# led-relay.net
KiCad netlist of a schematic drawn in Altium Designer
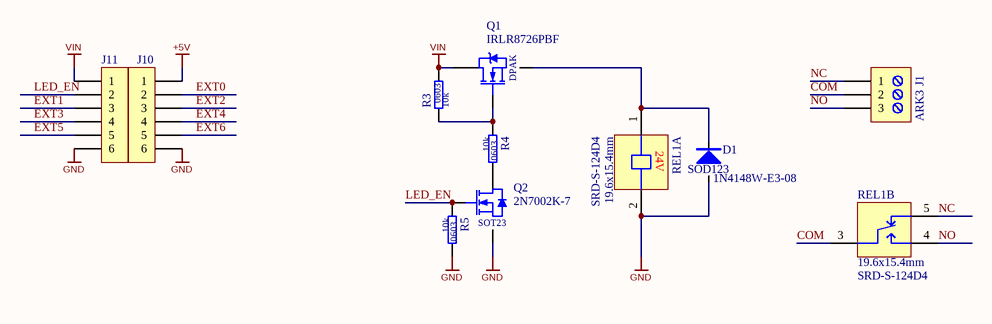
[diagram p0: led-relay.SchDoc]

(export (version "E")
  (design (tool "Eeschema 10.0.6"))
  (components
    (comp (ref "D1")
      (value "1N4148W-E3-08")
      (footprint "SOD123")
      (fields
        (field (name "SCH_FOOTPRINT") "SOD123")
        (field (name "PART NUMBER") "D_1N4148W_0A15_75V_SOD123")
        (field (name "VOLTAGE") "75")
        (field (name "MANUFACTURER") "Vishay")
      )
      (libsource (lib "Library") (part "D"))
    )
    (comp (ref "J1")
      (value "ARK3")
      (footprint "J_ARK3")
      (description "ARK Screw terminal, 3-Pin")
      (fields
        (field (name "SCH_FOOTPRINT") "ARK3")
        (field (name "PART NUMBER") "J_TB-5.0-P-3P")
        (field (name "MANUFACTURER") "DEGSON ELECTRONICS")
      )
      (libsource (lib "Library") (part "J_ARK3"))
    )
    (comp (ref "J10")
      (value "Goldpin")
      (footprint "P_HEADER_1x6_2.54")
      (description "Pin Header")
      (fields (field (name "PART NUMBER") "P_HEADER_1x6_2.54") (field (name "MANUFACTURER") "Connfly"))
      (libsource (lib "Library") (part "P_HEADER_1x6"))
    )
    (comp (ref "J11")
      (value "Goldpin")
      (footprint "P_HEADER_1x6_2.54")
      (description "Pin Header")
      (fields (field (name "PART NUMBER") "P_HEADER_1x6_2.54") (field (name "MANUFACTURER") "Connfly"))
      (libsource (lib "") (part "P_HEADER_1x6_1"))
    )
    (comp (ref "Q1")
      (value "IRLR8726PBF")
      (footprint "DPAK_TO252-3_SC63_M")
      (fields
        (field (name "SCH_FOOTPRINT") "DPAK")
        (field (name "PART NUMBER") "QNS_IRLR8726PBF")
        (field (name "VOLTAGE") "30V")
        (field (name "MANUFACTURER") "Infineon")
      )
      (libsource (lib "Library") (part "QNS_GDS"))
    )
    (comp (ref "Q2")
      (value "2N7002K-7")
      (footprint "SOT23_TO236_SC59")
      (fields
        (field (name "SCH_FOOTPRINT") "SOT23")
        (field (name "PART NUMBER") "QN_2N7002K-7")
        (field (name "VOLTAGE") "60V")
        (field (name "MANUFACTURER") "Diodes Inc")
      )
      (libsource (lib "Library") (part "QN_GSD"))
    )
    (comp (ref "R3")
      (value "10k")
      (footprint "R_0603_1608")
      (fields
        (field (name "SCH_FOOTPRINT") "0603")
        (field (name "PART NUMBER") "R_10k_0603_1")
        (field (name "VOLTAGE") "75V")
        (field (name "POWER") "100mW")
      )
      (libsource (lib "Library") (part "R"))
    )
    (comp (ref "R4")
      (value "10k")
      (footprint "R_0603_1608")
      (fields
        (field (name "SCH_FOOTPRINT") "0603")
        (field (name "PART NUMBER") "R_10k_0603_1")
        (field (name "VOLTAGE") "75V")
        (field (name "POWER") "100mW")
      )
      (libsource (lib "Library") (part "R"))
    )
    (comp (ref "R5")
      (value "10k")
      (footprint "R_0603_1608")
      (fields
        (field (name "SCH_FOOTPRINT") "0603")
        (field (name "PART NUMBER") "R_10k_0603_1")
        (field (name "VOLTAGE") "75V")
        (field (name "POWER") "100mW")
      )
      (libsource (lib "Library") (part "R"))
    )
    (comp (ref "REL1")
      (value "SRD-S-124D4")
      (footprint "SRD-S-124D4")
      (fields
        (field (name "SCH_FOOTPRINT") "19.6x15.4mm")
        (field (name "PART NUMBER") "REL_SRD-S-124D4")
        (field (name "VOLTAGE") "24V")
        (field (name "MANUFACTURER") "Sanyou")
      )
      (libsource (lib "Library") (part "REL_SRD-S-124D4"))
    )
  )
  (nets
    (net (code "1") (name "+5V") (class "Default")
      (node (ref "J10") (pin "1") (pinfunction "1_1") (pintype "passive"))
    )
    (net (code "2") (name "/COM") (class "Default")
      (node (ref "J1") (pin "2") (pinfunction "2_2") (pintype "passive"))
      (node (ref "REL1") (pin "3") (pinfunction "3_3") (pintype "passive"))
    )
    (net (code "3") (name "/EXT0") (class "Default")
      (node (ref "J10") (pin "2") (pinfunction "2_2") (pintype "passive"))
    )
    (net (code "4") (name "/EXT1") (class "Default")
      (node (ref "J11") (pin "3") (pinfunction "3_3") (pintype "passive"))
    )
    (net (code "5") (name "/EXT2") (class "Default")
      (node (ref "J10") (pin "3") (pinfunction "3_3") (pintype "passive"))
    )
    (net (code "6") (name "/EXT3") (class "Default")
      (node (ref "J11") (pin "4") (pinfunction "4_4") (pintype "passive"))
    )
    (net (code "7") (name "/EXT4") (class "Default")
      (node (ref "J10") (pin "4") (pinfunction "4_4") (pintype "passive"))
    )
    (net (code "8") (name "/EXT5") (class "Default")
      (node (ref "J11") (pin "5") (pinfunction "5_5") (pintype "passive"))
    )
    (net (code "9") (name "/EXT6") (class "Default")
      (node (ref "J10") (pin "5") (pinfunction "5_5") (pintype "passive"))
    )
    (net (code "10") (name "/LED_EN") (class "Default")
      (node (ref "J11") (pin "2") (pinfunction "2_2") (pintype "passive"))
      (node (ref "Q2") (pin "1") (pinfunction "G_1") (pintype "passive"))
      (node (ref "R5") (pin "1") (pinfunction "1_1") (pintype "passive"))
    )
    (net (code "11") (name "/NC") (class "Default")
      (node (ref "J1") (pin "1") (pinfunction "1_1") (pintype "passive"))
      (node (ref "REL1") (pin "5") (pinfunction "5_5") (pintype "passive"))
    )
    (net (code "12") (name "/NO") (class "Default")
      (node (ref "J1") (pin "3") (pinfunction "3_3") (pintype "passive"))
      (node (ref "REL1") (pin "4") (pinfunction "8_4") (pintype "passive"))
    )
    (net (code "13") (name "GND") (class "Default")
      (node (ref "D1") (pin "2") (pintype "passive"))
      (node (ref "J10") (pin "6") (pinfunction "6_6") (pintype "passive"))
      (node (ref "J11") (pin "6") (pinfunction "6_6") (pintype "passive"))
      (node (ref "Q2") (pin "2") (pinfunction "S_2") (pintype "passive"))
      (node (ref "R5") (pin "2") (pinfunction "2_2") (pintype "passive"))
      (node (ref "REL1") (pin "2") (pinfunction "2_2") (pintype "passive"))
    )
    (net (code "14") (name "Net-(Q1-G)") (class "Default")
      (node (ref "Q1") (pin "1") (pinfunction "G_1") (pintype "passive"))
      (node (ref "R3") (pin "1") (pinfunction "1_1") (pintype "passive"))
      (node (ref "R4") (pin "1") (pinfunction "1_1") (pintype "passive"))
    )
    (net (code "15") (name "Net-(Q1-S)") (class "Default")
      (node (ref "D1") (pin "1") (pintype "passive"))
      (node (ref "Q1") (pin "3") (pinfunction "S_3") (pintype "passive"))
      (node (ref "REL1") (pin "1") (pinfunction "1_1") (pintype "passive"))
    )
    (net (code "16") (name "Net-(Q2-D)") (class "Default")
      (node (ref "Q2") (pin "3") (pinfunction "D_3") (pintype "passive"))
      (node (ref "R4") (pin "2") (pinfunction "2_2") (pintype "passive"))
    )
    (net (code "17") (name "VIN") (class "Default")
      (node (ref "J11") (pin "1") (pinfunction "1_1") (pintype "passive"))
      (node (ref "Q1") (pin "2") (pinfunction "D_2") (pintype "passive"))
      (node (ref "R3") (pin "2") (pinfunction "2_2") (pintype "passive"))
    )
  )
)
